# USB_Experiment_Board.net
KiCad netlist of a schematic drawn in EAGLE
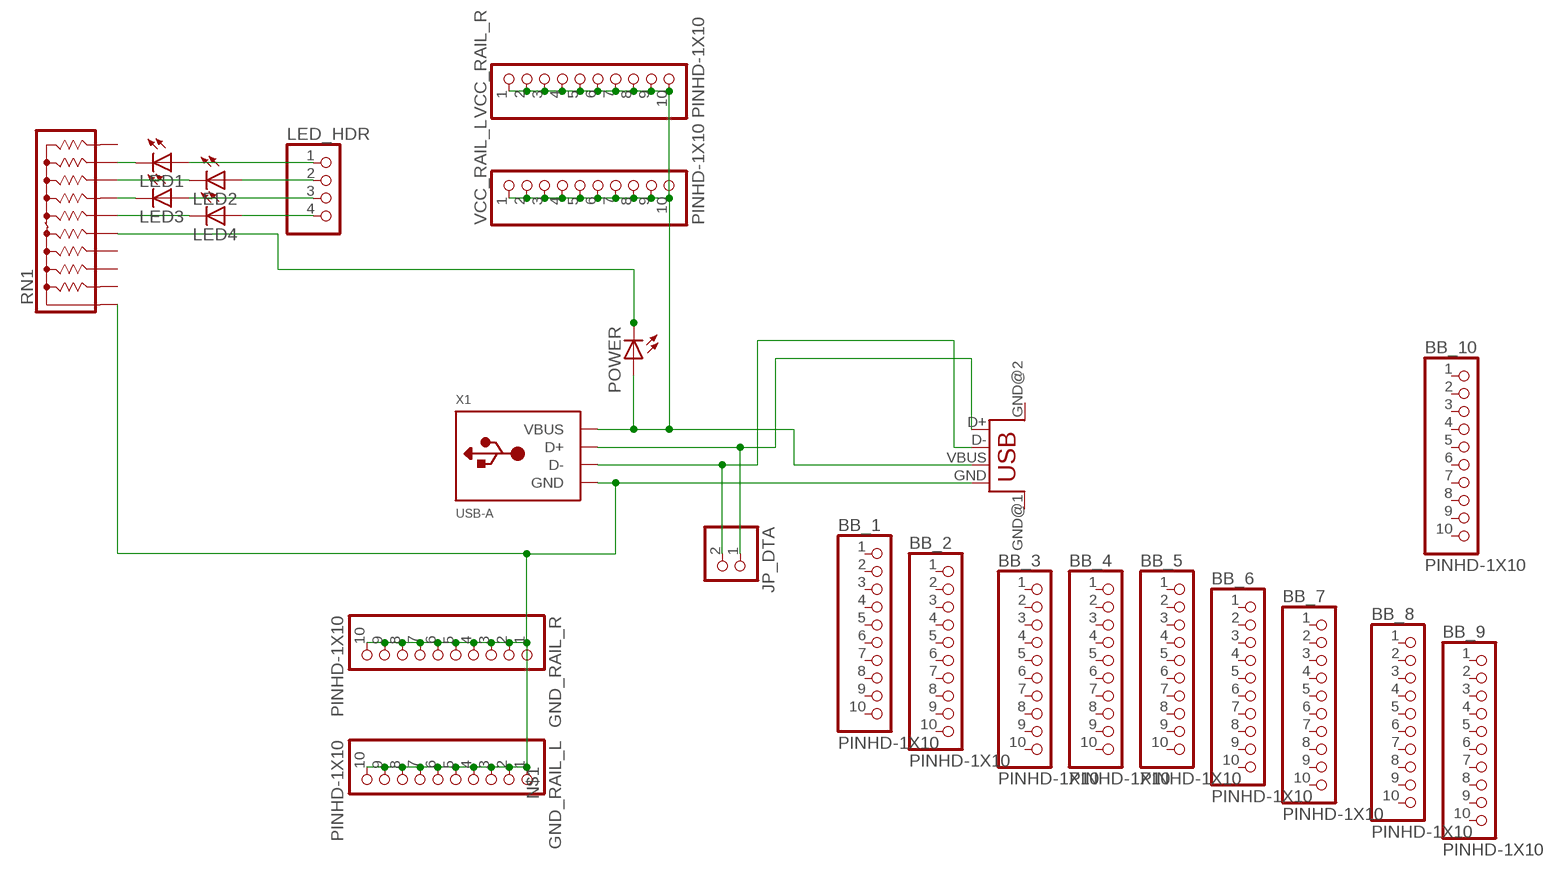
[diagram p0: schematic, sheet 1]

(export (version "E")
  (design (tool "Eeschema 10.0.6"))
  (components
    (comp (ref "BB_1")
      (value "PINHD-1X10")
      (footprint "eagle-import:1X10-BIG")
      (libsource (lib "eagle-import") (part "PINHD-1X10"))
    )
    (comp (ref "BB_2")
      (value "PINHD-1X10")
      (footprint "eagle-import:1X10-BIG")
      (libsource (lib "eagle-import") (part "PINHD-1X10"))
    )
    (comp (ref "BB_3")
      (value "PINHD-1X10")
      (footprint "eagle-import:1X10-BIG")
      (libsource (lib "eagle-import") (part "PINHD-1X10"))
    )
    (comp (ref "BB_4")
      (value "PINHD-1X10")
      (footprint "eagle-import:1X10-BIG")
      (libsource (lib "eagle-import") (part "PINHD-1X10"))
    )
    (comp (ref "BB_5")
      (value "PINHD-1X10")
      (footprint "eagle-import:1X10-BIG")
      (libsource (lib "eagle-import") (part "PINHD-1X10"))
    )
    (comp (ref "BB_6")
      (value "PINHD-1X10")
      (footprint "eagle-import:1X10-BIG")
      (libsource (lib "eagle-import") (part "PINHD-1X10"))
    )
    (comp (ref "BB_7")
      (value "PINHD-1X10")
      (footprint "eagle-import:1X10-BIG")
      (libsource (lib "eagle-import") (part "PINHD-1X10"))
    )
    (comp (ref "BB_8")
      (value "PINHD-1X10")
      (footprint "eagle-import:1X10-BIG")
      (libsource (lib "eagle-import") (part "PINHD-1X10"))
    )
    (comp (ref "BB_9")
      (value "PINHD-1X10")
      (footprint "eagle-import:1X10-BIG")
      (libsource (lib "eagle-import") (part "PINHD-1X10"))
    )
    (comp (ref "BB_10")
      (value "PINHD-1X10")
      (footprint "eagle-import:1X10-BIG")
      (libsource (lib "eagle-import") (part "PINHD-1X10"))
    )
    (comp (ref "GND_RAIL_L")
      (value "PINHD-1X10")
      (footprint "eagle-import:1X10-BIG")
      (libsource (lib "eagle-import") (part "PINHD-1X10"))
    )
    (comp (ref "GND_RAIL_R")
      (value "PINHD-1X10")
      (footprint "eagle-import:1X10-BIG")
      (libsource (lib "eagle-import") (part "PINHD-1X10"))
    )
    (comp (ref "JP_DTA")
      (value "PINHD-1X2")
      (footprint "eagle-import:1X02")
      (libsource (lib "eagle-import") (part "PINHD-1X2"))
    )
    (comp (ref "LED1")
      (value "LEDSMT1206")
      (footprint "eagle-import:1206")
      (libsource (lib "eagle-import") (part "LEDSMT1206"))
    )
    (comp (ref "LED2")
      (value "LEDSMT1206")
      (footprint "eagle-import:1206")
      (libsource (lib "eagle-import") (part "LEDSMT1206"))
    )
    (comp (ref "LED3")
      (value "LEDSMT1206")
      (footprint "eagle-import:1206")
      (libsource (lib "eagle-import") (part "LEDSMT1206"))
    )
    (comp (ref "LED4")
      (value "LEDSMT1206")
      (footprint "eagle-import:1206")
      (libsource (lib "eagle-import") (part "LEDSMT1206"))
    )
    (comp (ref "LED_HDR")
      (value "PINHD-1X4")
      (footprint "eagle-import:1X04")
      (libsource (lib "eagle-import") (part "PINHD-1X4"))
    )
    (comp (ref "POWER")
      (value "LEDSMT1206")
      (footprint "eagle-import:1206")
      (libsource (lib "eagle-import") (part "LEDSMT1206"))
    )
    (comp (ref "RN1")
      (value "4610X")
      (footprint "eagle-import:SIP10")
      (libsource (lib "eagle-import") (part "4610X"))
    )
    (comp (ref "U$1")
      (value "USB")
      (footprint "eagle-import:USB-FEMALE-A-PTH")
      (libsource (lib "eagle-import") (part "USB"))
    )
    (comp (ref "VCC_RAIL_L")
      (value "PINHD-1X10")
      (footprint "eagle-import:1X10-BIG")
      (libsource (lib "eagle-import") (part "PINHD-1X10"))
    )
    (comp (ref "VCC_RAIL_R")
      (value "PINHD-1X10")
      (footprint "eagle-import:1X10-BIG")
      (libsource (lib "eagle-import") (part "PINHD-1X10"))
    )
    (comp (ref "X1")
      (value "USB-A")
      (footprint "eagle-import:MOLEX_480371000")
      (libsource (lib "eagle-import") (part "USB-A"))
    )
  )
  (nets
    (net (code "1") (name "/N$1") (class "Default")
      (node (ref "GND_RAIL_L") (pin "1") (pinfunction "1_1") (pintype "passive"))
      (node (ref "GND_RAIL_L") (pin "10") (pinfunction "10_10") (pintype "passive"))
      (node (ref "GND_RAIL_L") (pin "2") (pinfunction "2_2") (pintype "passive"))
      (node (ref "GND_RAIL_L") (pin "3") (pinfunction "3_3") (pintype "passive"))
      (node (ref "GND_RAIL_L") (pin "4") (pinfunction "4_4") (pintype "passive"))
      (node (ref "GND_RAIL_L") (pin "5") (pinfunction "5_5") (pintype "passive"))
      (node (ref "GND_RAIL_L") (pin "6") (pinfunction "6_6") (pintype "passive"))
      (node (ref "GND_RAIL_L") (pin "7") (pinfunction "7_7") (pintype "passive"))
      (node (ref "GND_RAIL_L") (pin "8") (pinfunction "8_8") (pintype "passive"))
      (node (ref "GND_RAIL_L") (pin "9") (pinfunction "9_9") (pintype "passive"))
      (node (ref "GND_RAIL_R") (pin "1") (pinfunction "1_1") (pintype "passive"))
      (node (ref "GND_RAIL_R") (pin "10") (pinfunction "10_10") (pintype "passive"))
      (node (ref "GND_RAIL_R") (pin "2") (pinfunction "2_2") (pintype "passive"))
      (node (ref "GND_RAIL_R") (pin "3") (pinfunction "3_3") (pintype "passive"))
      (node (ref "GND_RAIL_R") (pin "4") (pinfunction "4_4") (pintype "passive"))
      (node (ref "GND_RAIL_R") (pin "5") (pinfunction "5_5") (pintype "passive"))
      (node (ref "GND_RAIL_R") (pin "6") (pinfunction "6_6") (pintype "passive"))
      (node (ref "GND_RAIL_R") (pin "7") (pinfunction "7_7") (pintype "passive"))
      (node (ref "GND_RAIL_R") (pin "8") (pinfunction "8_8") (pintype "passive"))
      (node (ref "GND_RAIL_R") (pin "9") (pinfunction "9_9") (pintype "passive"))
      (node (ref "RN1") (pin "1") (pinfunction "1_1") (pintype "passive"))
      (node (ref "U$1") (pin "GND") (pinfunction "GND_GND") (pintype "bidirectional"))
      (node (ref "X1") (pin "4") (pinfunction "GND_4") (pintype "power_in"))
    )
    (net (code "2") (name "Net-(LED1-PadA)") (class "Default")
      (node (ref "LED1") (pin "A") (pinfunction "A_A") (pintype "passive"))
      (node (ref "LED_HDR") (pin "1") (pinfunction "1_1") (pintype "passive"))
    )
    (net (code "3") (name "Net-(LED1-PadC)") (class "Default")
      (node (ref "LED1") (pin "C") (pinfunction "C_C") (pintype "passive"))
      (node (ref "RN1") (pin "9") (pinfunction "9_9") (pintype "passive"))
    )
    (net (code "4") (name "Net-(LED2-PadA)") (class "Default")
      (node (ref "LED2") (pin "A") (pinfunction "A_A") (pintype "passive"))
      (node (ref "LED_HDR") (pin "2") (pinfunction "2_2") (pintype "passive"))
    )
    (net (code "5") (name "Net-(LED2-PadC)") (class "Default")
      (node (ref "LED2") (pin "C") (pinfunction "C_C") (pintype "passive"))
      (node (ref "RN1") (pin "8") (pinfunction "8_8") (pintype "passive"))
    )
    (net (code "6") (name "Net-(LED3-PadA)") (class "Default")
      (node (ref "LED3") (pin "A") (pinfunction "A_A") (pintype "passive"))
      (node (ref "LED_HDR") (pin "3") (pinfunction "3_3") (pintype "passive"))
    )
    (net (code "7") (name "Net-(LED3-PadC)") (class "Default")
      (node (ref "LED3") (pin "C") (pinfunction "C_C") (pintype "passive"))
      (node (ref "RN1") (pin "7") (pinfunction "7_7") (pintype "passive"))
    )
    (net (code "8") (name "Net-(LED4-PadA)") (class "Default")
      (node (ref "LED4") (pin "A") (pinfunction "A_A") (pintype "passive"))
      (node (ref "LED_HDR") (pin "4") (pinfunction "4_4") (pintype "passive"))
    )
    (net (code "9") (name "Net-(LED4-PadC)") (class "Default")
      (node (ref "LED4") (pin "C") (pinfunction "C_C") (pintype "passive"))
      (node (ref "RN1") (pin "6") (pinfunction "6_6") (pintype "passive"))
    )
    (net (code "10") (name "Net-(POWER-PadC)") (class "Default")
      (node (ref "POWER") (pin "C") (pinfunction "C_C") (pintype "passive"))
      (node (ref "RN1") (pin "5") (pinfunction "5_5") (pintype "passive"))
    )
    (net (code "11") (name "Net-(X1-D+)") (class "Default")
      (node (ref "JP_DTA") (pin "1") (pinfunction "1_1") (pintype "passive"))
      (node (ref "U$1") (pin "D+") (pinfunction "D+_D+") (pintype "bidirectional"))
      (node (ref "X1") (pin "3") (pinfunction "D+_3") (pintype "bidirectional"))
    )
    (net (code "12") (name "Net-(X1-D-)") (class "Default")
      (node (ref "JP_DTA") (pin "2") (pinfunction "2_2") (pintype "passive"))
      (node (ref "U$1") (pin "D-") (pinfunction "D-_D-") (pintype "bidirectional"))
      (node (ref "X1") (pin "2") (pinfunction "D-_2") (pintype "bidirectional"))
    )
    (net (code "13") (name "Net-(X1-VBUS)") (class "Default")
      (node (ref "POWER") (pin "A") (pinfunction "A_A") (pintype "passive"))
      (node (ref "U$1") (pin "VBUS") (pinfunction "VBUS_VBUS") (pintype "bidirectional"))
      (node (ref "VCC_RAIL_L") (pin "1") (pinfunction "1_1") (pintype "passive"))
      (node (ref "VCC_RAIL_L") (pin "10") (pinfunction "10_10") (pintype "passive"))
      (node (ref "VCC_RAIL_L") (pin "2") (pinfunction "2_2") (pintype "passive"))
      (node (ref "VCC_RAIL_L") (pin "3") (pinfunction "3_3") (pintype "passive"))
      (node (ref "VCC_RAIL_L") (pin "4") (pinfunction "4_4") (pintype "passive"))
      (node (ref "VCC_RAIL_L") (pin "5") (pinfunction "5_5") (pintype "passive"))
      (node (ref "VCC_RAIL_L") (pin "6") (pinfunction "6_6") (pintype "passive"))
      (node (ref "VCC_RAIL_L") (pin "7") (pinfunction "7_7") (pintype "passive"))
      (node (ref "VCC_RAIL_L") (pin "8") (pinfunction "8_8") (pintype "passive"))
      (node (ref "VCC_RAIL_L") (pin "9") (pinfunction "9_9") (pintype "passive"))
      (node (ref "VCC_RAIL_R") (pin "1") (pinfunction "1_1") (pintype "passive"))
      (node (ref "VCC_RAIL_R") (pin "10") (pinfunction "10_10") (pintype "passive"))
      (node (ref "VCC_RAIL_R") (pin "2") (pinfunction "2_2") (pintype "passive"))
      (node (ref "VCC_RAIL_R") (pin "3") (pinfunction "3_3") (pintype "passive"))
      (node (ref "VCC_RAIL_R") (pin "4") (pinfunction "4_4") (pintype "passive"))
      (node (ref "VCC_RAIL_R") (pin "5") (pinfunction "5_5") (pintype "passive"))
      (node (ref "VCC_RAIL_R") (pin "6") (pinfunction "6_6") (pintype "passive"))
      (node (ref "VCC_RAIL_R") (pin "7") (pinfunction "7_7") (pintype "passive"))
      (node (ref "VCC_RAIL_R") (pin "8") (pinfunction "8_8") (pintype "passive"))
      (node (ref "VCC_RAIL_R") (pin "9") (pinfunction "9_9") (pintype "passive"))
      (node (ref "X1") (pin "1") (pinfunction "VBUS_1") (pintype "power_in"))
    )
    (net (code "14") (name "unconnected-(BB_1-Pad1)") (class "Default")
      (node (ref "BB_1") (pin "1") (pinfunction "1_1") (pintype "passive"))
    )
    (net (code "15") (name "unconnected-(BB_1-Pad2)") (class "Default")
      (node (ref "BB_1") (pin "2") (pinfunction "2_2") (pintype "passive"))
    )
    (net (code "16") (name "unconnected-(BB_1-Pad3)") (class "Default")
      (node (ref "BB_1") (pin "3") (pinfunction "3_3") (pintype "passive"))
    )
    (net (code "17") (name "unconnected-(BB_1-Pad4)") (class "Default")
      (node (ref "BB_1") (pin "4") (pinfunction "4_4") (pintype "passive"))
    )
    (net (code "18") (name "unconnected-(BB_1-Pad5)") (class "Default")
      (node (ref "BB_1") (pin "5") (pinfunction "5_5") (pintype "passive"))
    )
    (net (code "19") (name "unconnected-(BB_1-Pad6)") (class "Default")
      (node (ref "BB_1") (pin "6") (pinfunction "6_6") (pintype "passive"))
    )
    (net (code "20") (name "unconnected-(BB_1-Pad7)") (class "Default")
      (node (ref "BB_1") (pin "7") (pinfunction "7_7") (pintype "passive"))
    )
    (net (code "21") (name "unconnected-(BB_1-Pad8)") (class "Default")
      (node (ref "BB_1") (pin "8") (pinfunction "8_8") (pintype "passive"))
    )
    (net (code "22") (name "unconnected-(BB_1-Pad9)") (class "Default")
      (node (ref "BB_1") (pin "9") (pinfunction "9_9") (pintype "passive"))
    )
    (net (code "23") (name "unconnected-(BB_1-Pad10)") (class "Default")
      (node (ref "BB_1") (pin "10") (pinfunction "10_10") (pintype "passive"))
    )
    (net (code "24") (name "unconnected-(BB_2-Pad1)") (class "Default")
      (node (ref "BB_2") (pin "1") (pinfunction "1_1") (pintype "passive"))
    )
    (net (code "25") (name "unconnected-(BB_2-Pad2)") (class "Default")
      (node (ref "BB_2") (pin "2") (pinfunction "2_2") (pintype "passive"))
    )
    (net (code "26") (name "unconnected-(BB_2-Pad3)") (class "Default")
      (node (ref "BB_2") (pin "3") (pinfunction "3_3") (pintype "passive"))
    )
    (net (code "27") (name "unconnected-(BB_2-Pad4)") (class "Default")
      (node (ref "BB_2") (pin "4") (pinfunction "4_4") (pintype "passive"))
    )
    (net (code "28") (name "unconnected-(BB_2-Pad5)") (class "Default")
      (node (ref "BB_2") (pin "5") (pinfunction "5_5") (pintype "passive"))
    )
    (net (code "29") (name "unconnected-(BB_2-Pad6)") (class "Default")
      (node (ref "BB_2") (pin "6") (pinfunction "6_6") (pintype "passive"))
    )
    (net (code "30") (name "unconnected-(BB_2-Pad7)") (class "Default")
      (node (ref "BB_2") (pin "7") (pinfunction "7_7") (pintype "passive"))
    )
    (net (code "31") (name "unconnected-(BB_2-Pad8)") (class "Default")
      (node (ref "BB_2") (pin "8") (pinfunction "8_8") (pintype "passive"))
    )
    (net (code "32") (name "unconnected-(BB_2-Pad9)") (class "Default")
      (node (ref "BB_2") (pin "9") (pinfunction "9_9") (pintype "passive"))
    )
    (net (code "33") (name "unconnected-(BB_2-Pad10)") (class "Default")
      (node (ref "BB_2") (pin "10") (pinfunction "10_10") (pintype "passive"))
    )
    (net (code "34") (name "unconnected-(BB_3-Pad1)") (class "Default")
      (node (ref "BB_3") (pin "1") (pinfunction "1_1") (pintype "passive"))
    )
    (net (code "35") (name "unconnected-(BB_3-Pad2)") (class "Default")
      (node (ref "BB_3") (pin "2") (pinfunction "2_2") (pintype "passive"))
    )
    (net (code "36") (name "unconnected-(BB_3-Pad3)") (class "Default")
      (node (ref "BB_3") (pin "3") (pinfunction "3_3") (pintype "passive"))
    )
    (net (code "37") (name "unconnected-(BB_3-Pad4)") (class "Default")
      (node (ref "BB_3") (pin "4") (pinfunction "4_4") (pintype "passive"))
    )
    (net (code "38") (name "unconnected-(BB_3-Pad5)") (class "Default")
      (node (ref "BB_3") (pin "5") (pinfunction "5_5") (pintype "passive"))
    )
    (net (code "39") (name "unconnected-(BB_3-Pad6)") (class "Default")
      (node (ref "BB_3") (pin "6") (pinfunction "6_6") (pintype "passive"))
    )
    (net (code "40") (name "unconnected-(BB_3-Pad7)") (class "Default")
      (node (ref "BB_3") (pin "7") (pinfunction "7_7") (pintype "passive"))
    )
    (net (code "41") (name "unconnected-(BB_3-Pad8)") (class "Default")
      (node (ref "BB_3") (pin "8") (pinfunction "8_8") (pintype "passive"))
    )
    (net (code "42") (name "unconnected-(BB_3-Pad9)") (class "Default")
      (node (ref "BB_3") (pin "9") (pinfunction "9_9") (pintype "passive"))
    )
    (net (code "43") (name "unconnected-(BB_3-Pad10)") (class "Default")
      (node (ref "BB_3") (pin "10") (pinfunction "10_10") (pintype "passive"))
    )
    (net (code "44") (name "unconnected-(BB_4-Pad1)") (class "Default")
      (node (ref "BB_4") (pin "1") (pinfunction "1_1") (pintype "passive"))
    )
    (net (code "45") (name "unconnected-(BB_4-Pad2)") (class "Default")
      (node (ref "BB_4") (pin "2") (pinfunction "2_2") (pintype "passive"))
    )
    (net (code "46") (name "unconnected-(BB_4-Pad3)") (class "Default")
      (node (ref "BB_4") (pin "3") (pinfunction "3_3") (pintype "passive"))
    )
    (net (code "47") (name "unconnected-(BB_4-Pad4)") (class "Default")
      (node (ref "BB_4") (pin "4") (pinfunction "4_4") (pintype "passive"))
    )
    (net (code "48") (name "unconnected-(BB_4-Pad5)") (class "Default")
      (node (ref "BB_4") (pin "5") (pinfunction "5_5") (pintype "passive"))
    )
    (net (code "49") (name "unconnected-(BB_4-Pad6)") (class "Default")
      (node (ref "BB_4") (pin "6") (pinfunction "6_6") (pintype "passive"))
    )
    (net (code "50") (name "unconnected-(BB_4-Pad7)") (class "Default")
      (node (ref "BB_4") (pin "7") (pinfunction "7_7") (pintype "passive"))
    )
    (net (code "51") (name "unconnected-(BB_4-Pad8)") (class "Default")
      (node (ref "BB_4") (pin "8") (pinfunction "8_8") (pintype "passive"))
    )
    (net (code "52") (name "unconnected-(BB_4-Pad9)") (class "Default")
      (node (ref "BB_4") (pin "9") (pinfunction "9_9") (pintype "passive"))
    )
    (net (code "53") (name "unconnected-(BB_4-Pad10)") (class "Default")
      (node (ref "BB_4") (pin "10") (pinfunction "10_10") (pintype "passive"))
    )
    (net (code "54") (name "unconnected-(BB_5-Pad1)") (class "Default")
      (node (ref "BB_5") (pin "1") (pinfunction "1_1") (pintype "passive"))
    )
    (net (code "55") (name "unconnected-(BB_5-Pad2)") (class "Default")
      (node (ref "BB_5") (pin "2") (pinfunction "2_2") (pintype "passive"))
    )
    (net (code "56") (name "unconnected-(BB_5-Pad3)") (class "Default")
      (node (ref "BB_5") (pin "3") (pinfunction "3_3") (pintype "passive"))
    )
    (net (code "57") (name "unconnected-(BB_5-Pad4)") (class "Default")
      (node (ref "BB_5") (pin "4") (pinfunction "4_4") (pintype "passive"))
    )
    (net (code "58") (name "unconnected-(BB_5-Pad5)") (class "Default")
      (node (ref "BB_5") (pin "5") (pinfunction "5_5") (pintype "passive"))
    )
    (net (code "59") (name "unconnected-(BB_5-Pad6)") (class "Default")
      (node (ref "BB_5") (pin "6") (pinfunction "6_6") (pintype "passive"))
    )
    (net (code "60") (name "unconnected-(BB_5-Pad7)") (class "Default")
      (node (ref "BB_5") (pin "7") (pinfunction "7_7") (pintype "passive"))
    )
    (net (code "61") (name "unconnected-(BB_5-Pad8)") (class "Default")
      (node (ref "BB_5") (pin "8") (pinfunction "8_8") (pintype "passive"))
    )
    (net (code "62") (name "unconnected-(BB_5-Pad9)") (class "Default")
      (node (ref "BB_5") (pin "9") (pinfunction "9_9") (pintype "passive"))
    )
    (net (code "63") (name "unconnected-(BB_5-Pad10)") (class "Default")
      (node (ref "BB_5") (pin "10") (pinfunction "10_10") (pintype "passive"))
    )
    (net (code "64") (name "unconnected-(BB_6-Pad1)") (class "Default")
      (node (ref "BB_6") (pin "1") (pinfunction "1_1") (pintype "passive"))
    )
    (net (code "65") (name "unconnected-(BB_6-Pad2)") (class "Default")
      (node (ref "BB_6") (pin "2") (pinfunction "2_2") (pintype "passive"))
    )
    (net (code "66") (name "unconnected-(BB_6-Pad3)") (class "Default")
      (node (ref "BB_6") (pin "3") (pinfunction "3_3") (pintype "passive"))
    )
    (net (code "67") (name "unconnected-(BB_6-Pad4)") (class "Default")
      (node (ref "BB_6") (pin "4") (pinfunction "4_4") (pintype "passive"))
    )
    (net (code "68") (name "unconnected-(BB_6-Pad5)") (class "Default")
      (node (ref "BB_6") (pin "5") (pinfunction "5_5") (pintype "passive"))
    )
    (net (code "69") (name "unconnected-(BB_6-Pad6)") (class "Default")
      (node (ref "BB_6") (pin "6") (pinfunction "6_6") (pintype "passive"))
    )
    (net (code "70") (name "unconnected-(BB_6-Pad7)") (class "Default")
      (node (ref "BB_6") (pin "7") (pinfunction "7_7") (pintype "passive"))
    )
    (net (code "71") (name "unconnected-(BB_6-Pad8)") (class "Default")
      (node (ref "BB_6") (pin "8") (pinfunction "8_8") (pintype "passive"))
    )
    (net (code "72") (name "unconnected-(BB_6-Pad9)") (class "Default")
      (node (ref "BB_6") (pin "9") (pinfunction "9_9") (pintype "passive"))
    )
    (net (code "73") (name "unconnected-(BB_6-Pad10)") (class "Default")
      (node (ref "BB_6") (pin "10") (pinfunction "10_10") (pintype "passive"))
    )
    (net (code "74") (name "unconnected-(BB_7-Pad1)") (class "Default")
      (node (ref "BB_7") (pin "1") (pinfunction "1_1") (pintype "passive"))
    )
    (net (code "75") (name "unconnected-(BB_7-Pad2)") (class "Default")
      (node (ref "BB_7") (pin "2") (pinfunction "2_2") (pintype "passive"))
    )
    (net (code "76") (name "unconnected-(BB_7-Pad3)") (class "Default")
      (node (ref "BB_7") (pin "3") (pinfunction "3_3") (pintype "passive"))
    )
    (net (code "77") (name "unconnected-(BB_7-Pad4)") (class "Default")
      (node (ref "BB_7") (pin "4") (pinfunction "4_4") (pintype "passive"))
    )
    (net (code "78") (name "unconnected-(BB_7-Pad5)") (class "Default")
      (node (ref "BB_7") (pin "5") (pinfunction "5_5") (pintype "passive"))
    )
    (net (code "79") (name "unconnected-(BB_7-Pad6)") (class "Default")
      (node (ref "BB_7") (pin "6") (pinfunction "6_6") (pintype "passive"))
    )
    (net (code "80") (name "unconnected-(BB_7-Pad7)") (class "Default")
      (node (ref "BB_7") (pin "7") (pinfunction "7_7") (pintype "passive"))
    )
    (net (code "81") (name "unconnected-(BB_7-Pad8)") (class "Default")
      (node (ref "BB_7") (pin "8") (pinfunction "8_8") (pintype "passive"))
    )
    (net (code "82") (name "unconnected-(BB_7-Pad9)") (class "Default")
      (node (ref "BB_7") (pin "9") (pinfunction "9_9") (pintype "passive"))
    )
    (net (code "83") (name "unconnected-(BB_7-Pad10)") (class "Default")
      (node (ref "BB_7") (pin "10") (pinfunction "10_10") (pintype "passive"))
    )
    (net (code "84") (name "unconnected-(BB_8-Pad1)") (class "Default")
      (node (ref "BB_8") (pin "1") (pinfunction "1_1") (pintype "passive"))
    )
    (net (code "85") (name "unconnected-(BB_8-Pad2)") (class "Default")
      (node (ref "BB_8") (pin "2") (pinfunction "2_2") (pintype "passive"))
    )
    (net (code "86") (name "unconnected-(BB_8-Pad3)") (class "Default")
      (node (ref "BB_8") (pin "3") (pinfunction "3_3") (pintype "passive"))
    )
    (net (code "87") (name "unconnected-(BB_8-Pad4)") (class "Default")
      (node (ref "BB_8") (pin "4") (pinfunction "4_4") (pintype "passive"))
    )
    (net (code "88") (name "unconnected-(BB_8-Pad5)") (class "Default")
      (node (ref "BB_8") (pin "5") (pinfunction "5_5") (pintype "passive"))
    )
    (net (code "89") (name "unconnected-(BB_8-Pad6)") (class "Default")
      (node (ref "BB_8") (pin "6") (pinfunction "6_6") (pintype "passive"))
    )
    (net (code "90") (name "unconnected-(BB_8-Pad7)") (class "Default")
      (node (ref "BB_8") (pin "7") (pinfunction "7_7") (pintype "passive"))
    )
    (net (code "91") (name "unconnected-(BB_8-Pad8)") (class "Default")
      (node (ref "BB_8") (pin "8") (pinfunction "8_8") (pintype "passive"))
    )
    (net (code "92") (name "unconnected-(BB_8-Pad9)") (class "Default")
      (node (ref "BB_8") (pin "9") (pinfunction "9_9") (pintype "passive"))
    )
    (net (code "93") (name "unconnected-(BB_8-Pad10)") (class "Default")
      (node (ref "BB_8") (pin "10") (pinfunction "10_10") (pintype "passive"))
    )
    (net (code "94") (name "unconnected-(BB_9-Pad1)") (class "Default")
      (node (ref "BB_9") (pin "1") (pinfunction "1_1") (pintype "passive"))
    )
    (net (code "95") (name "unconnected-(BB_9-Pad2)") (class "Default")
      (node (ref "BB_9") (pin "2") (pinfunction "2_2") (pintype "passive"))
    )
    (net (code "96") (name "unconnected-(BB_9-Pad3)") (class "Default")
      (node (ref "BB_9") (pin "3") (pinfunction "3_3") (pintype "passive"))
    )
    (net (code "97") (name "unconnected-(BB_9-Pad4)") (class "Default")
      (node (ref "BB_9") (pin "4") (pinfunction "4_4") (pintype "passive"))
    )
    (net (code "98") (name "unconnected-(BB_9-Pad5)") (class "Default")
      (node (ref "BB_9") (pin "5") (pinfunction "5_5") (pintype "passive"))
    )
    (net (code "99") (name "unconnected-(BB_9-Pad6)") (class "Default")
      (node (ref "BB_9") (pin "6") (pinfunction "6_6") (pintype "passive"))
    )
    (net (code "100") (name "unconnected-(BB_9-Pad7)") (class "Default")
      (node (ref "BB_9") (pin "7") (pinfunction "7_7") (pintype "passive"))
    )
    (net (code "101") (name "unconnected-(BB_9-Pad8)") (class "Default")
      (node (ref "BB_9") (pin "8") (pinfunction "8_8") (pintype "passive"))
    )
    (net (code "102") (name "unconnected-(BB_9-Pad9)") (class "Default")
      (node (ref "BB_9") (pin "9") (pinfunction "9_9") (pintype "passive"))
    )
    (net (code "103") (name "unconnected-(BB_9-Pad10)") (class "Default")
      (node (ref "BB_9") (pin "10") (pinfunction "10_10") (pintype "passive"))
    )
    (net (code "104") (name "unconnected-(BB_10-Pad1)") (class "Default")
      (node (ref "BB_10") (pin "1") (pinfunction "1_1") (pintype "passive"))
    )
    (net (code "105") (name "unconnected-(BB_10-Pad2)") (class "Default")
      (node (ref "BB_10") (pin "2") (pinfunction "2_2") (pintype "passive"))
    )
    (net (code "106") (name "unconnected-(BB_10-Pad3)") (class "Default")
      (node (ref "BB_10") (pin "3") (pinfunction "3_3") (pintype "passive"))
    )
    (net (code "107") (name "unconnected-(BB_10-Pad4)") (class "Default")
      (node (ref "BB_10") (pin "4") (pinfunction "4_4") (pintype "passive"))
    )
    (net (code "108") (name "unconnected-(BB_10-Pad5)") (class "Default")
      (node (ref "BB_10") (pin "5") (pinfunction "5_5") (pintype "passive"))
    )
    (net (code "109") (name "unconnected-(BB_10-Pad6)") (class "Default")
      (node (ref "BB_10") (pin "6") (pinfunction "6_6") (pintype "passive"))
    )
    (net (code "110") (name "unconnected-(BB_10-Pad7)") (class "Default")
      (node (ref "BB_10") (pin "7") (pinfunction "7_7") (pintype "passive"))
    )
    (net (code "111") (name "unconnected-(BB_10-Pad8)") (class "Default")
      (node (ref "BB_10") (pin "8") (pinfunction "8_8") (pintype "passive"))
    )
    (net (code "112") (name "unconnected-(BB_10-Pad9)") (class "Default")
      (node (ref "BB_10") (pin "9") (pinfunction "9_9") (pintype "passive"))
    )
    (net (code "113") (name "unconnected-(BB_10-Pad10)") (class "Default")
      (node (ref "BB_10") (pin "10") (pinfunction "10_10") (pintype "passive"))
    )
    (net (code "114") (name "unconnected-(RN1-Pad2)") (class "Default")
      (node (ref "RN1") (pin "2") (pinfunction "2_2") (pintype "passive"))
    )
    (net (code "115") (name "unconnected-(RN1-Pad3)") (class "Default")
      (node (ref "RN1") (pin "3") (pinfunction "3_3") (pintype "passive"))
    )
    (net (code "116") (name "unconnected-(RN1-Pad4)") (class "Default")
      (node (ref "RN1") (pin "4") (pinfunction "4_4") (pintype "passive"))
    )
    (net (code "117") (name "unconnected-(RN1-Pad10)") (class "Default")
      (node (ref "RN1") (pin "10") (pinfunction "10_10") (pintype "passive"))
    )
    (net (code "118") (name "unconnected-(U$1-GND-PadGND@1)") (class "Default")
      (node (ref "U$1") (pin "GND@1") (pinfunction "GND_GND@1") (pintype "bidirectional"))
    )
    (net (code "119") (name "unconnected-(U$1-GND-PadGND@2)") (class "Default")
      (node (ref "U$1") (pin "GND@2") (pinfunction "GND_GND@2") (pintype "bidirectional"))
    )
  )
)
